# AD_3_V1_01.net
KiCad netlist of a schematic drawn in Altium Designer
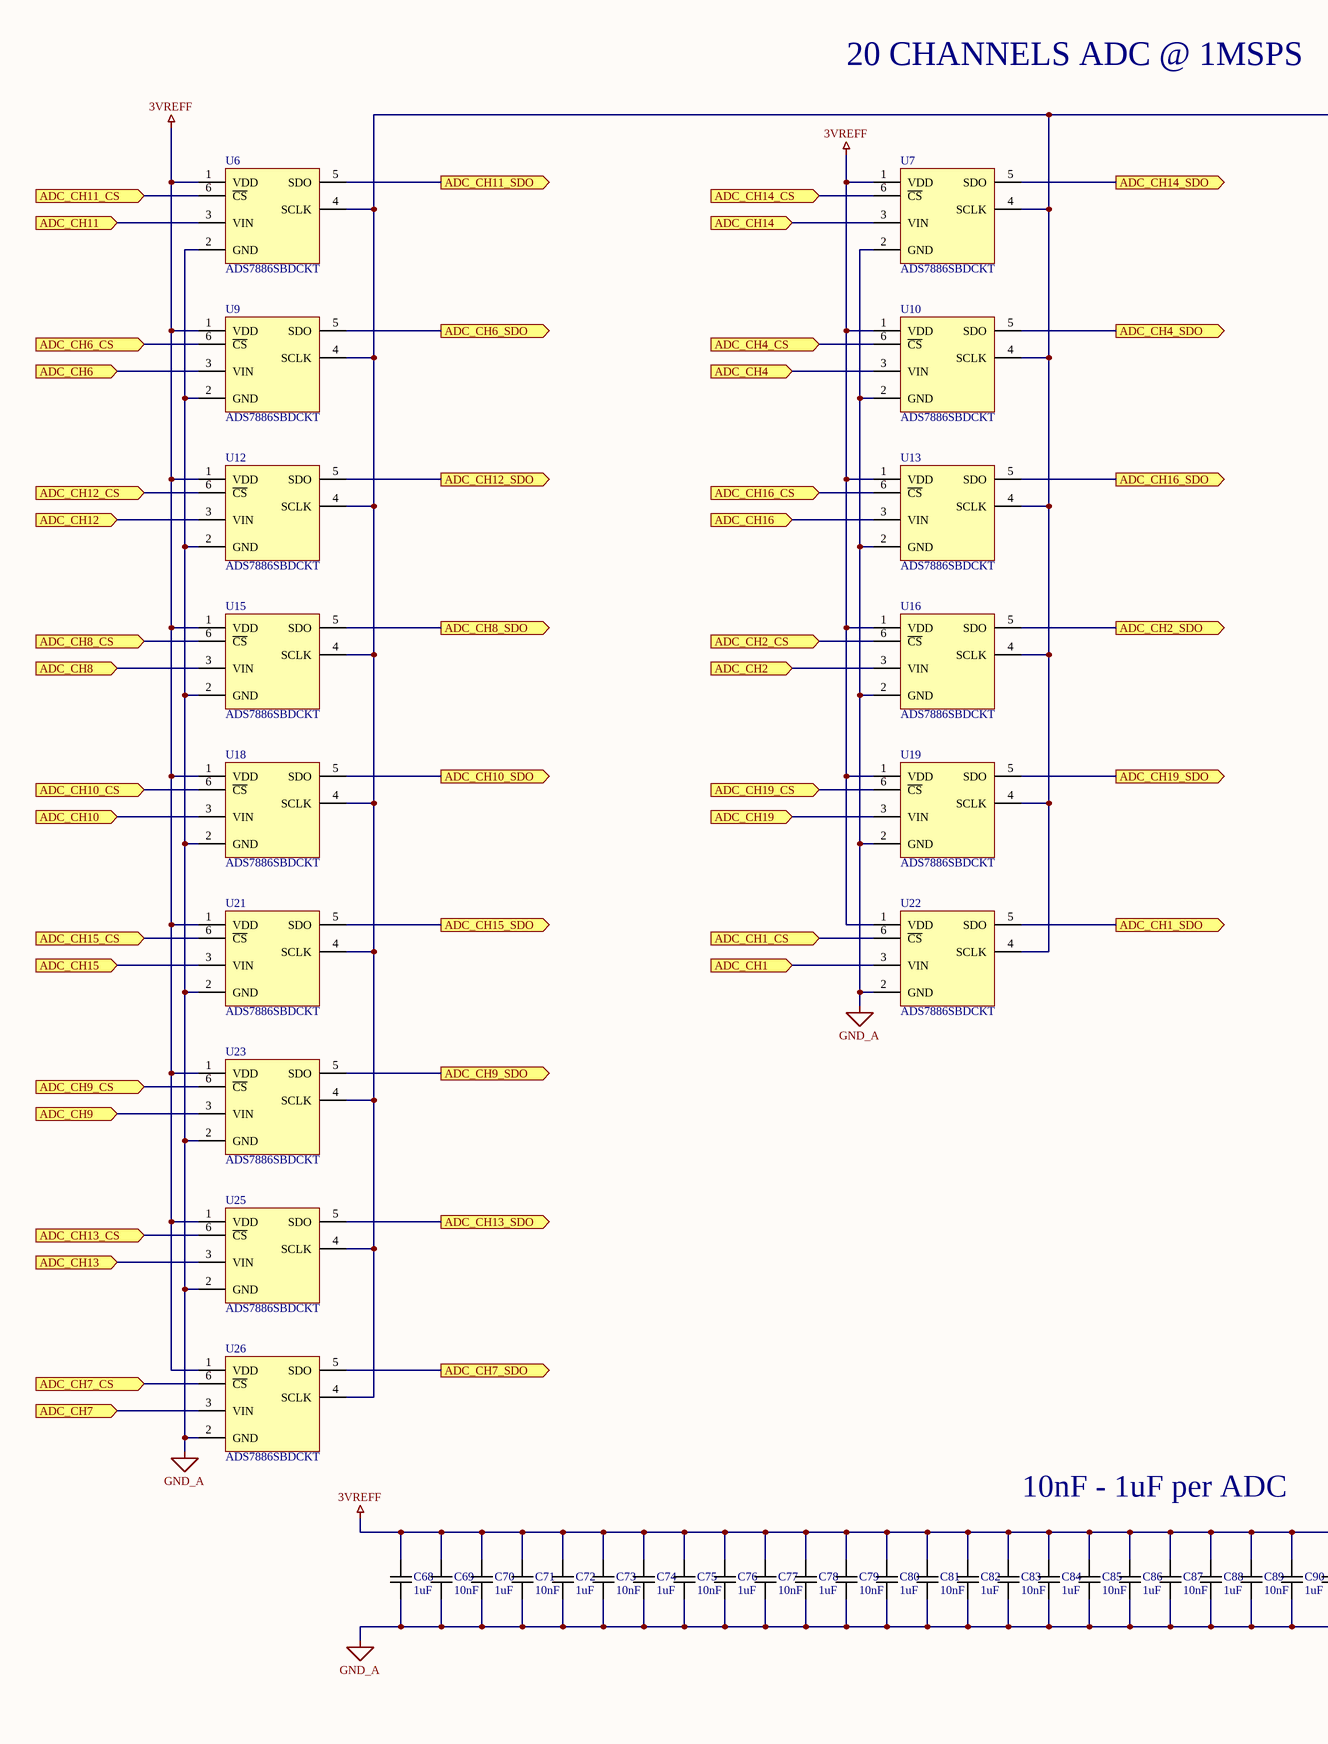
[diagram p0: AD_3_V1_01.SchDoc, left]
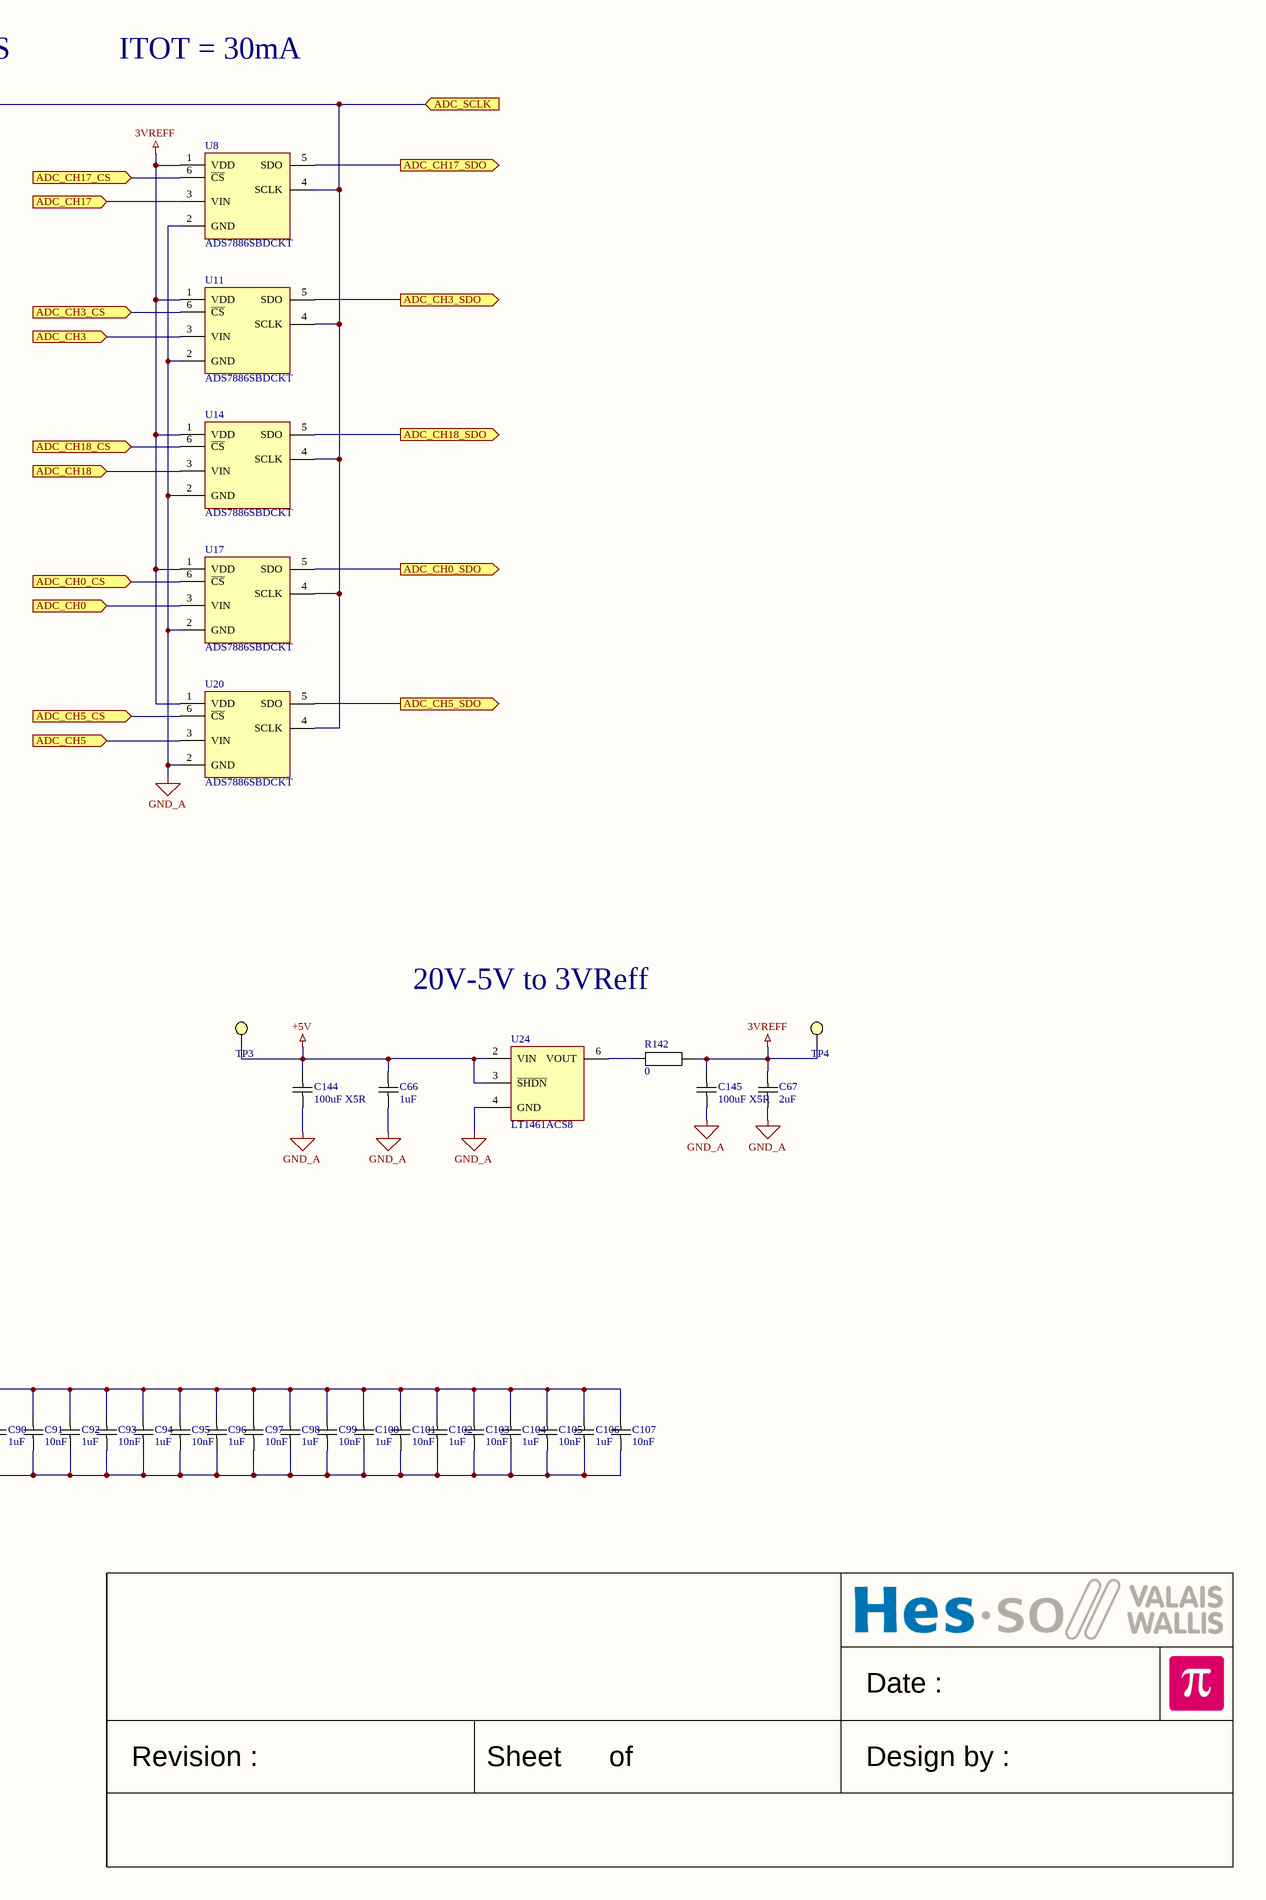
[diagram p1: AD_3_V1_01.SchDoc, right]

(export (version "E")
  (design (tool "Eeschema 10.0.6"))
  (components
    (comp (ref "C66")
      (value "1uF")
      (footprint "CAPACITOR 1608 REFLOW")
      (description "Capacitor")
      (libsource (lib "Capacitor") (part "Capacitor"))
    )
    (comp (ref "C67")
      (value "2uF")
      (footprint "CAPACITOR 1608 REFLOW")
      (description "Capacitor")
      (libsource (lib "Capacitor") (part "Capacitor"))
    )
    (comp (ref "C68")
      (value "1uF")
      (footprint "CAPACITOR 1608 REFLOW")
      (description "Capacitor")
      (libsource (lib "Capacitor") (part "Capacitor"))
    )
    (comp (ref "C69")
      (value "10nF")
      (footprint "CAPACITOR 1608 REFLOW")
      (description "Capacitor")
      (libsource (lib "Capacitor") (part "Capacitor"))
    )
    (comp (ref "C70")
      (value "1uF")
      (footprint "CAPACITOR 1608 REFLOW")
      (description "Capacitor")
      (libsource (lib "Capacitor") (part "Capacitor"))
    )
    (comp (ref "C71")
      (value "10nF")
      (footprint "CAPACITOR 1608 REFLOW")
      (description "Capacitor")
      (libsource (lib "Capacitor") (part "Capacitor"))
    )
    (comp (ref "C72")
      (value "1uF")
      (footprint "CAPACITOR 1608 REFLOW")
      (description "Capacitor")
      (libsource (lib "Capacitor") (part "Capacitor"))
    )
    (comp (ref "C73")
      (value "10nF")
      (footprint "CAPACITOR 1608 REFLOW")
      (description "Capacitor")
      (libsource (lib "Capacitor") (part "Capacitor"))
    )
    (comp (ref "C74")
      (value "1uF")
      (footprint "CAPACITOR 1608 REFLOW")
      (description "Capacitor")
      (libsource (lib "Capacitor") (part "Capacitor"))
    )
    (comp (ref "C75")
      (value "10nF")
      (footprint "CAPACITOR 1608 REFLOW")
      (description "Capacitor")
      (libsource (lib "Capacitor") (part "Capacitor"))
    )
    (comp (ref "C76")
      (value "1uF")
      (footprint "CAPACITOR 1608 REFLOW")
      (description "Capacitor")
      (libsource (lib "Capacitor") (part "Capacitor"))
    )
    (comp (ref "C77")
      (value "10nF")
      (footprint "CAPACITOR 1608 REFLOW")
      (description "Capacitor")
      (libsource (lib "Capacitor") (part "Capacitor"))
    )
    (comp (ref "C78")
      (value "1uF")
      (footprint "CAPACITOR 1608 REFLOW")
      (description "Capacitor")
      (libsource (lib "Capacitor") (part "Capacitor"))
    )
    (comp (ref "C79")
      (value "10nF")
      (footprint "CAPACITOR 1608 REFLOW")
      (description "Capacitor")
      (libsource (lib "Capacitor") (part "Capacitor"))
    )
    (comp (ref "C80")
      (value "1uF")
      (footprint "CAPACITOR 1608 REFLOW")
      (description "Capacitor")
      (libsource (lib "Capacitor") (part "Capacitor"))
    )
    (comp (ref "C81")
      (value "10nF")
      (footprint "CAPACITOR 1608 REFLOW")
      (description "Capacitor")
      (libsource (lib "Capacitor") (part "Capacitor"))
    )
    (comp (ref "C82")
      (value "1uF")
      (footprint "CAPACITOR 1608 REFLOW")
      (description "Capacitor")
      (libsource (lib "Capacitor") (part "Capacitor"))
    )
    (comp (ref "C83")
      (value "10nF")
      (footprint "CAPACITOR 1608 REFLOW")
      (description "Capacitor")
      (libsource (lib "Capacitor") (part "Capacitor"))
    )
    (comp (ref "C84")
      (value "1uF")
      (footprint "CAPACITOR 1608 REFLOW")
      (description "Capacitor")
      (libsource (lib "Capacitor") (part "Capacitor"))
    )
    (comp (ref "C85")
      (value "10nF")
      (footprint "CAPACITOR 1608 REFLOW")
      (description "Capacitor")
      (libsource (lib "Capacitor") (part "Capacitor"))
    )
    (comp (ref "C86")
      (value "1uF")
      (footprint "CAPACITOR 1608 REFLOW")
      (description "Capacitor")
      (libsource (lib "Capacitor") (part "Capacitor"))
    )
    (comp (ref "C87")
      (value "10nF")
      (footprint "CAPACITOR 1608 REFLOW")
      (description "Capacitor")
      (libsource (lib "Capacitor") (part "Capacitor"))
    )
    (comp (ref "C88")
      (value "1uF")
      (footprint "CAPACITOR 1608 REFLOW")
      (description "Capacitor")
      (libsource (lib "Capacitor") (part "Capacitor"))
    )
    (comp (ref "C89")
      (value "10nF")
      (footprint "CAPACITOR 1608 REFLOW")
      (description "Capacitor")
      (libsource (lib "Capacitor") (part "Capacitor"))
    )
    (comp (ref "C90")
      (value "1uF")
      (footprint "CAPACITOR 1608 REFLOW")
      (description "Capacitor")
      (libsource (lib "Capacitor") (part "Capacitor"))
    )
    (comp (ref "C91")
      (value "10nF")
      (footprint "CAPACITOR 1608 REFLOW")
      (description "Capacitor")
      (libsource (lib "Capacitor") (part "Capacitor"))
    )
    (comp (ref "C92")
      (value "1uF")
      (footprint "CAPACITOR 1608 REFLOW")
      (description "Capacitor")
      (libsource (lib "Capacitor") (part "Capacitor"))
    )
    (comp (ref "C93")
      (value "10nF")
      (footprint "CAPACITOR 1608 REFLOW")
      (description "Capacitor")
      (libsource (lib "Capacitor") (part "Capacitor"))
    )
    (comp (ref "C94")
      (value "1uF")
      (footprint "CAPACITOR 1608 REFLOW")
      (description "Capacitor")
      (libsource (lib "Capacitor") (part "Capacitor"))
    )
    (comp (ref "C95")
      (value "10nF")
      (footprint "CAPACITOR 1608 REFLOW")
      (description "Capacitor")
      (libsource (lib "Capacitor") (part "Capacitor"))
    )
    (comp (ref "C96")
      (value "1uF")
      (footprint "CAPACITOR 1608 REFLOW")
      (description "Capacitor")
      (libsource (lib "Capacitor") (part "Capacitor"))
    )
    (comp (ref "C97")
      (value "10nF")
      (footprint "CAPACITOR 1608 REFLOW")
      (description "Capacitor")
      (libsource (lib "Capacitor") (part "Capacitor"))
    )
    (comp (ref "C98")
      (value "1uF")
      (footprint "CAPACITOR 1608 REFLOW")
      (description "Capacitor")
      (libsource (lib "Capacitor") (part "Capacitor"))
    )
    (comp (ref "C99")
      (value "10nF")
      (footprint "CAPACITOR 1608 REFLOW")
      (description "Capacitor")
      (libsource (lib "Capacitor") (part "Capacitor"))
    )
    (comp (ref "C100")
      (value "1uF")
      (footprint "CAPACITOR 1608 REFLOW")
      (description "Capacitor")
      (libsource (lib "Capacitor") (part "Capacitor"))
    )
    (comp (ref "C101")
      (value "10nF")
      (footprint "CAPACITOR 1608 REFLOW")
      (description "Capacitor")
      (libsource (lib "Capacitor") (part "Capacitor"))
    )
    (comp (ref "C102")
      (value "1uF")
      (footprint "CAPACITOR 1608 REFLOW")
      (description "Capacitor")
      (libsource (lib "Capacitor") (part "Capacitor"))
    )
    (comp (ref "C103")
      (value "10nF")
      (footprint "CAPACITOR 1608 REFLOW")
      (description "Capacitor")
      (libsource (lib "Capacitor") (part "Capacitor"))
    )
    (comp (ref "C104")
      (value "1uF")
      (footprint "CAPACITOR 1608 REFLOW")
      (description "Capacitor")
      (libsource (lib "Capacitor") (part "Capacitor"))
    )
    (comp (ref "C105")
      (value "10nF")
      (footprint "CAPACITOR 1608 REFLOW")
      (description "Capacitor")
      (libsource (lib "Capacitor") (part "Capacitor"))
    )
    (comp (ref "C106")
      (value "1uF")
      (footprint "CAPACITOR 1608 REFLOW")
      (description "Capacitor")
      (libsource (lib "Capacitor") (part "Capacitor"))
    )
    (comp (ref "C107")
      (value "10nF")
      (footprint "CAPACITOR 1608 REFLOW")
      (description "Capacitor")
      (libsource (lib "Capacitor") (part "Capacitor"))
    )
    (comp (ref "C144")
      (value "100uF X5R")
      (footprint "CAPACITOR 3216 REFLOW")
      (description "Capacitor")
      (libsource (lib "Capacitor") (part "Capacitor"))
    )
    (comp (ref "C145")
      (value "100uF X5R")
      (footprint "CAPACITOR 3216 REFLOW")
      (description "Capacitor")
      (libsource (lib "Capacitor") (part "Capacitor"))
    )
    (comp (ref "R142")
      (value "0")
      (footprint "RESISTOR 1608 REFLOW")
      (description "Resistor 1% 50V 100mW 1608(0603)")
      (libsource (lib "Resistor") (part "Resistor"))
    )
    (comp (ref "TP3")
      (value "*")
      (footprint "Test Point Keystone Miniature RED")
      (description "Test Point")
      (libsource (lib "Testpoint") (part "Test Point"))
    )
    (comp (ref "TP4")
      (value "*")
      (footprint "Test Point Keystone Miniature RED")
      (description "Test Point")
      (libsource (lib "Testpoint") (part "Test Point"))
    )
    (comp (ref "U6")
      (value "ADS7886SBDCKT")
      (footprint "SOT23-6 P0.95 C1.5x3.0 H1.3")
      (description "12-Bit, 1-MSPS, Micro-Power, Miniature SAR Analog-to-Digital Converters")
      (libsource (lib "Converter") (part "ADS7886SBDCKT"))
    )
    (comp (ref "U7")
      (value "ADS7886SBDCKT")
      (footprint "SOT23-6 P0.95 C1.5x3.0 H1.3")
      (description "12-Bit, 1-MSPS, Micro-Power, Miniature SAR Analog-to-Digital Converters")
      (libsource (lib "Converter") (part "ADS7886SBDCKT"))
    )
    (comp (ref "U8")
      (value "ADS7886SBDCKT")
      (footprint "SOT23-6 P0.95 C1.5x3.0 H1.3")
      (description "12-Bit, 1-MSPS, Micro-Power, Miniature SAR Analog-to-Digital Converters")
      (libsource (lib "Converter") (part "ADS7886SBDCKT"))
    )
    (comp (ref "U9")
      (value "ADS7886SBDCKT")
      (footprint "SOT23-6 P0.95 C1.5x3.0 H1.3")
      (description "12-Bit, 1-MSPS, Micro-Power, Miniature SAR Analog-to-Digital Converters")
      (libsource (lib "Converter") (part "ADS7886SBDCKT"))
    )
    (comp (ref "U10")
      (value "ADS7886SBDCKT")
      (footprint "SOT23-6 P0.95 C1.5x3.0 H1.3")
      (description "12-Bit, 1-MSPS, Micro-Power, Miniature SAR Analog-to-Digital Converters")
      (libsource (lib "Converter") (part "ADS7886SBDCKT"))
    )
    (comp (ref "U11")
      (value "ADS7886SBDCKT")
      (footprint "SOT23-6 P0.95 C1.5x3.0 H1.3")
      (description "12-Bit, 1-MSPS, Micro-Power, Miniature SAR Analog-to-Digital Converters")
      (libsource (lib "Converter") (part "ADS7886SBDCKT"))
    )
    (comp (ref "U12")
      (value "ADS7886SBDCKT")
      (footprint "SOT23-6 P0.95 C1.5x3.0 H1.3")
      (description "12-Bit, 1-MSPS, Micro-Power, Miniature SAR Analog-to-Digital Converters")
      (libsource (lib "Converter") (part "ADS7886SBDCKT"))
    )
    (comp (ref "U13")
      (value "ADS7886SBDCKT")
      (footprint "SOT23-6 P0.95 C1.5x3.0 H1.3")
      (description "12-Bit, 1-MSPS, Micro-Power, Miniature SAR Analog-to-Digital Converters")
      (libsource (lib "Converter") (part "ADS7886SBDCKT"))
    )
    (comp (ref "U14")
      (value "ADS7886SBDCKT")
      (footprint "SOT23-6 P0.95 C1.5x3.0 H1.3")
      (description "12-Bit, 1-MSPS, Micro-Power, Miniature SAR Analog-to-Digital Converters")
      (libsource (lib "Converter") (part "ADS7886SBDCKT"))
    )
    (comp (ref "U15")
      (value "ADS7886SBDCKT")
      (footprint "SOT23-6 P0.95 C1.5x3.0 H1.3")
      (description "12-Bit, 1-MSPS, Micro-Power, Miniature SAR Analog-to-Digital Converters")
      (libsource (lib "Converter") (part "ADS7886SBDCKT"))
    )
    (comp (ref "U16")
      (value "ADS7886SBDCKT")
      (footprint "SOT23-6 P0.95 C1.5x3.0 H1.3")
      (description "12-Bit, 1-MSPS, Micro-Power, Miniature SAR Analog-to-Digital Converters")
      (libsource (lib "Converter") (part "ADS7886SBDCKT"))
    )
    (comp (ref "U17")
      (value "ADS7886SBDCKT")
      (footprint "SOT23-6 P0.95 C1.5x3.0 H1.3")
      (description "12-Bit, 1-MSPS, Micro-Power, Miniature SAR Analog-to-Digital Converters")
      (libsource (lib "Converter") (part "ADS7886SBDCKT"))
    )
    (comp (ref "U18")
      (value "ADS7886SBDCKT")
      (footprint "SOT23-6 P0.95 C1.5x3.0 H1.3")
      (description "12-Bit, 1-MSPS, Micro-Power, Miniature SAR Analog-to-Digital Converters")
      (libsource (lib "Converter") (part "ADS7886SBDCKT"))
    )
    (comp (ref "U19")
      (value "ADS7886SBDCKT")
      (footprint "SOT23-6 P0.95 C1.5x3.0 H1.3")
      (description "12-Bit, 1-MSPS, Micro-Power, Miniature SAR Analog-to-Digital Converters")
      (libsource (lib "Converter") (part "ADS7886SBDCKT"))
    )
    (comp (ref "U20")
      (value "ADS7886SBDCKT")
      (footprint "SOT23-6 P0.95 C1.5x3.0 H1.3")
      (description "12-Bit, 1-MSPS, Micro-Power, Miniature SAR Analog-to-Digital Converters")
      (libsource (lib "Converter") (part "ADS7886SBDCKT"))
    )
    (comp (ref "U21")
      (value "ADS7886SBDCKT")
      (footprint "SOT23-6 P0.95 C1.5x3.0 H1.3")
      (description "12-Bit, 1-MSPS, Micro-Power, Miniature SAR Analog-to-Digital Converters")
      (libsource (lib "Converter") (part "ADS7886SBDCKT"))
    )
    (comp (ref "U22")
      (value "ADS7886SBDCKT")
      (footprint "SOT23-6 P0.95 C1.5x3.0 H1.3")
      (description "12-Bit, 1-MSPS, Micro-Power, Miniature SAR Analog-to-Digital Converters")
      (libsource (lib "Converter") (part "ADS7886SBDCKT"))
    )
    (comp (ref "U23")
      (value "ADS7886SBDCKT")
      (footprint "SOT23-6 P0.95 C1.5x3.0 H1.3")
      (description "12-Bit, 1-MSPS, Micro-Power, Miniature SAR Analog-to-Digital Converters")
      (libsource (lib "Converter") (part "ADS7886SBDCKT"))
    )
    (comp (ref "U24")
      (value "LT1461ACS8")
      (footprint "SO8 P1.27 C4.0X5.0 H1.75")
      (description "Micropower Precision Low Dropout Series Voltage Reference Family")
      (libsource (lib "Regulator") (part "LT1461ACS8"))
    )
    (comp (ref "U25")
      (value "ADS7886SBDCKT")
      (footprint "SOT23-6 P0.95 C1.5x3.0 H1.3")
      (description "12-Bit, 1-MSPS, Micro-Power, Miniature SAR Analog-to-Digital Converters")
      (libsource (lib "Converter") (part "ADS7886SBDCKT"))
    )
    (comp (ref "U26")
      (value "ADS7886SBDCKT")
      (footprint "SOT23-6 P0.95 C1.5x3.0 H1.3")
      (description "12-Bit, 1-MSPS, Micro-Power, Miniature SAR Analog-to-Digital Converters")
      (libsource (lib "Converter") (part "ADS7886SBDCKT"))
    )
  )
  (nets
    (net (code "1") (name "+5V") (class "Default")
      (node (ref "C144") (pin "2") (pinfunction "2_2") (pintype "passive"))
      (node (ref "C66") (pin "2") (pinfunction "2_2") (pintype "passive"))
      (node (ref "TP3") (pin "1") (pinfunction "1_1") (pintype "passive"))
      (node (ref "U24") (pin "2") (pinfunction "VIN_2") (pintype "passive"))
      (node (ref "U24") (pin "3") (pinfunction "~{SHDN}_3") (pintype "passive"))
    )
    (net (code "2") (name "/ADC_CH0") (class "Default")
      (node (ref "U17") (pin "3") (pinfunction "VIN_3") (pintype "passive"))
    )
    (net (code "3") (name "/ADC_CH0_CS") (class "Default")
      (node (ref "U17") (pin "6") (pinfunction "~{CS}_6") (pintype "passive"))
    )
    (net (code "4") (name "/ADC_CH0_SDO") (class "Default")
      (node (ref "U17") (pin "5") (pinfunction "SDO_5") (pintype "passive"))
    )
    (net (code "5") (name "/ADC_CH1") (class "Default")
      (node (ref "U22") (pin "3") (pinfunction "VIN_3") (pintype "passive"))
    )
    (net (code "6") (name "/ADC_CH1_CS") (class "Default")
      (node (ref "U22") (pin "6") (pinfunction "~{CS}_6") (pintype "passive"))
    )
    (net (code "7") (name "/ADC_CH1_SDO") (class "Default")
      (node (ref "U22") (pin "5") (pinfunction "SDO_5") (pintype "passive"))
    )
    (net (code "8") (name "/ADC_CH2") (class "Default")
      (node (ref "U16") (pin "3") (pinfunction "VIN_3") (pintype "passive"))
    )
    (net (code "9") (name "/ADC_CH2_CS") (class "Default")
      (node (ref "U16") (pin "6") (pinfunction "~{CS}_6") (pintype "passive"))
    )
    (net (code "10") (name "/ADC_CH2_SDO") (class "Default")
      (node (ref "U16") (pin "5") (pinfunction "SDO_5") (pintype "passive"))
    )
    (net (code "11") (name "/ADC_CH3") (class "Default")
      (node (ref "U11") (pin "3") (pinfunction "VIN_3") (pintype "passive"))
    )
    (net (code "12") (name "/ADC_CH3_CS") (class "Default")
      (node (ref "U11") (pin "6") (pinfunction "~{CS}_6") (pintype "passive"))
    )
    (net (code "13") (name "/ADC_CH3_SDO") (class "Default")
      (node (ref "U11") (pin "5") (pinfunction "SDO_5") (pintype "passive"))
    )
    (net (code "14") (name "/ADC_CH4") (class "Default")
      (node (ref "U10") (pin "3") (pinfunction "VIN_3") (pintype "passive"))
    )
    (net (code "15") (name "/ADC_CH4_CS") (class "Default")
      (node (ref "U10") (pin "6") (pinfunction "~{CS}_6") (pintype "passive"))
    )
    (net (code "16") (name "/ADC_CH4_SDO") (class "Default")
      (node (ref "U10") (pin "5") (pinfunction "SDO_5") (pintype "passive"))
    )
    (net (code "17") (name "/ADC_CH5") (class "Default")
      (node (ref "U20") (pin "3") (pinfunction "VIN_3") (pintype "passive"))
    )
    (net (code "18") (name "/ADC_CH5_CS") (class "Default")
      (node (ref "U20") (pin "6") (pinfunction "~{CS}_6") (pintype "passive"))
    )
    (net (code "19") (name "/ADC_CH5_SDO") (class "Default")
      (node (ref "U20") (pin "5") (pinfunction "SDO_5") (pintype "passive"))
    )
    (net (code "20") (name "/ADC_CH6") (class "Default")
      (node (ref "U9") (pin "3") (pinfunction "VIN_3") (pintype "passive"))
    )
    (net (code "21") (name "/ADC_CH6_CS") (class "Default")
      (node (ref "U9") (pin "6") (pinfunction "~{CS}_6") (pintype "passive"))
    )
    (net (code "22") (name "/ADC_CH6_SDO") (class "Default")
      (node (ref "U9") (pin "5") (pinfunction "SDO_5") (pintype "passive"))
    )
    (net (code "23") (name "/ADC_CH7") (class "Default")
      (node (ref "U26") (pin "3") (pinfunction "VIN_3") (pintype "passive"))
    )
    (net (code "24") (name "/ADC_CH7_CS") (class "Default")
      (node (ref "U26") (pin "6") (pinfunction "~{CS}_6") (pintype "passive"))
    )
    (net (code "25") (name "/ADC_CH7_SDO") (class "Default")
      (node (ref "U26") (pin "5") (pinfunction "SDO_5") (pintype "passive"))
    )
    (net (code "26") (name "/ADC_CH8") (class "Default")
      (node (ref "U15") (pin "3") (pinfunction "VIN_3") (pintype "passive"))
    )
    (net (code "27") (name "/ADC_CH8_CS") (class "Default")
      (node (ref "U15") (pin "6") (pinfunction "~{CS}_6") (pintype "passive"))
    )
    (net (code "28") (name "/ADC_CH8_SDO") (class "Default")
      (node (ref "U15") (pin "5") (pinfunction "SDO_5") (pintype "passive"))
    )
    (net (code "29") (name "/ADC_CH9") (class "Default")
      (node (ref "U23") (pin "3") (pinfunction "VIN_3") (pintype "passive"))
    )
    (net (code "30") (name "/ADC_CH9_CS") (class "Default")
      (node (ref "U23") (pin "6") (pinfunction "~{CS}_6") (pintype "passive"))
    )
    (net (code "31") (name "/ADC_CH9_SDO") (class "Default")
      (node (ref "U23") (pin "5") (pinfunction "SDO_5") (pintype "passive"))
    )
    (net (code "32") (name "/ADC_CH10") (class "Default")
      (node (ref "U18") (pin "3") (pinfunction "VIN_3") (pintype "passive"))
    )
    (net (code "33") (name "/ADC_CH10_CS") (class "Default")
      (node (ref "U18") (pin "6") (pinfunction "~{CS}_6") (pintype "passive"))
    )
    (net (code "34") (name "/ADC_CH10_SDO") (class "Default")
      (node (ref "U18") (pin "5") (pinfunction "SDO_5") (pintype "passive"))
    )
    (net (code "35") (name "/ADC_CH11") (class "Default")
      (node (ref "U6") (pin "3") (pinfunction "VIN_3") (pintype "passive"))
    )
    (net (code "36") (name "/ADC_CH11_CS") (class "Default")
      (node (ref "U6") (pin "6") (pinfunction "~{CS}_6") (pintype "passive"))
    )
    (net (code "37") (name "/ADC_CH11_SDO") (class "Default")
      (node (ref "U6") (pin "5") (pinfunction "SDO_5") (pintype "passive"))
    )
    (net (code "38") (name "/ADC_CH12") (class "Default")
      (node (ref "U12") (pin "3") (pinfunction "VIN_3") (pintype "passive"))
    )
    (net (code "39") (name "/ADC_CH12_CS") (class "Default")
      (node (ref "U12") (pin "6") (pinfunction "~{CS}_6") (pintype "passive"))
    )
    (net (code "40") (name "/ADC_CH12_SDO") (class "Default")
      (node (ref "U12") (pin "5") (pinfunction "SDO_5") (pintype "passive"))
    )
    (net (code "41") (name "/ADC_CH13") (class "Default")
      (node (ref "U25") (pin "3") (pinfunction "VIN_3") (pintype "passive"))
    )
    (net (code "42") (name "/ADC_CH13_CS") (class "Default")
      (node (ref "U25") (pin "6") (pinfunction "~{CS}_6") (pintype "passive"))
    )
    (net (code "43") (name "/ADC_CH13_SDO") (class "Default")
      (node (ref "U25") (pin "5") (pinfunction "SDO_5") (pintype "passive"))
    )
    (net (code "44") (name "/ADC_CH14") (class "Default")
      (node (ref "U7") (pin "3") (pinfunction "VIN_3") (pintype "passive"))
    )
    (net (code "45") (name "/ADC_CH14_CS") (class "Default")
      (node (ref "U7") (pin "6") (pinfunction "~{CS}_6") (pintype "passive"))
    )
    (net (code "46") (name "/ADC_CH14_SDO") (class "Default")
      (node (ref "U7") (pin "5") (pinfunction "SDO_5") (pintype "passive"))
    )
    (net (code "47") (name "/ADC_CH15") (class "Default")
      (node (ref "U21") (pin "3") (pinfunction "VIN_3") (pintype "passive"))
    )
    (net (code "48") (name "/ADC_CH15_CS") (class "Default")
      (node (ref "U21") (pin "6") (pinfunction "~{CS}_6") (pintype "passive"))
    )
    (net (code "49") (name "/ADC_CH15_SDO") (class "Default")
      (node (ref "U21") (pin "5") (pinfunction "SDO_5") (pintype "passive"))
    )
    (net (code "50") (name "/ADC_CH16") (class "Default")
      (node (ref "U13") (pin "3") (pinfunction "VIN_3") (pintype "passive"))
    )
    (net (code "51") (name "/ADC_CH16_CS") (class "Default")
      (node (ref "U13") (pin "6") (pinfunction "~{CS}_6") (pintype "passive"))
    )
    (net (code "52") (name "/ADC_CH16_SDO") (class "Default")
      (node (ref "U13") (pin "5") (pinfunction "SDO_5") (pintype "passive"))
    )
    (net (code "53") (name "/ADC_CH17") (class "Default")
      (node (ref "U8") (pin "3") (pinfunction "VIN_3") (pintype "passive"))
    )
    (net (code "54") (name "/ADC_CH17_CS") (class "Default")
      (node (ref "U8") (pin "6") (pinfunction "~{CS}_6") (pintype "passive"))
    )
    (net (code "55") (name "/ADC_CH17_SDO") (class "Default")
      (node (ref "U8") (pin "5") (pinfunction "SDO_5") (pintype "passive"))
    )
    (net (code "56") (name "/ADC_CH18") (class "Default")
      (node (ref "U14") (pin "3") (pinfunction "VIN_3") (pintype "passive"))
    )
    (net (code "57") (name "/ADC_CH18_CS") (class "Default")
      (node (ref "U14") (pin "6") (pinfunction "~{CS}_6") (pintype "passive"))
    )
    (net (code "58") (name "/ADC_CH18_SDO") (class "Default")
      (node (ref "U14") (pin "5") (pinfunction "SDO_5") (pintype "passive"))
    )
    (net (code "59") (name "/ADC_CH19") (class "Default")
      (node (ref "U19") (pin "3") (pinfunction "VIN_3") (pintype "passive"))
    )
    (net (code "60") (name "/ADC_CH19_CS") (class "Default")
      (node (ref "U19") (pin "6") (pinfunction "~{CS}_6") (pintype "passive"))
    )
    (net (code "61") (name "/ADC_CH19_SDO") (class "Default")
      (node (ref "U19") (pin "5") (pinfunction "SDO_5") (pintype "passive"))
    )
    (net (code "62") (name "/ADC_SCLK") (class "Default")
      (node (ref "U10") (pin "4") (pinfunction "SCLK_4") (pintype "passive"))
      (node (ref "U11") (pin "4") (pinfunction "SCLK_4") (pintype "passive"))
      (node (ref "U12") (pin "4") (pinfunction "SCLK_4") (pintype "passive"))
      (node (ref "U13") (pin "4") (pinfunction "SCLK_4") (pintype "passive"))
      (node (ref "U14") (pin "4") (pinfunction "SCLK_4") (pintype "passive"))
      (node (ref "U15") (pin "4") (pinfunction "SCLK_4") (pintype "passive"))
      (node (ref "U16") (pin "4") (pinfunction "SCLK_4") (pintype "passive"))
      (node (ref "U17") (pin "4") (pinfunction "SCLK_4") (pintype "passive"))
      (node (ref "U18") (pin "4") (pinfunction "SCLK_4") (pintype "passive"))
      (node (ref "U19") (pin "4") (pinfunction "SCLK_4") (pintype "passive"))
      (node (ref "U20") (pin "4") (pinfunction "SCLK_4") (pintype "passive"))
      (node (ref "U21") (pin "4") (pinfunction "SCLK_4") (pintype "passive"))
      (node (ref "U22") (pin "4") (pinfunction "SCLK_4") (pintype "passive"))
      (node (ref "U23") (pin "4") (pinfunction "SCLK_4") (pintype "passive"))
      (node (ref "U25") (pin "4") (pinfunction "SCLK_4") (pintype "passive"))
      (node (ref "U26") (pin "4") (pinfunction "SCLK_4") (pintype "passive"))
      (node (ref "U6") (pin "4") (pinfunction "SCLK_4") (pintype "passive"))
      (node (ref "U7") (pin "4") (pinfunction "SCLK_4") (pintype "passive"))
      (node (ref "U8") (pin "4") (pinfunction "SCLK_4") (pintype "passive"))
      (node (ref "U9") (pin "4") (pinfunction "SCLK_4") (pintype "passive"))
    )
    (net (code "63") (name "3VREFF") (class "Default")
      (node (ref "C100") (pin "2") (pinfunction "2_2") (pintype "passive"))
      (node (ref "C101") (pin "2") (pinfunction "2_2") (pintype "passive"))
      (node (ref "C102") (pin "2") (pinfunction "2_2") (pintype "passive"))
      (node (ref "C103") (pin "2") (pinfunction "2_2") (pintype "passive"))
      (node (ref "C104") (pin "2") (pinfunction "2_2") (pintype "passive"))
      (node (ref "C105") (pin "2") (pinfunction "2_2") (pintype "passive"))
      (node (ref "C106") (pin "2") (pinfunction "2_2") (pintype "passive"))
      (node (ref "C107") (pin "2") (pinfunction "2_2") (pintype "passive"))
      (node (ref "C145") (pin "2") (pinfunction "2_2") (pintype "passive"))
      (node (ref "C67") (pin "2") (pinfunction "2_2") (pintype "passive"))
      (node (ref "C68") (pin "2") (pinfunction "2_2") (pintype "passive"))
      (node (ref "C69") (pin "2") (pinfunction "2_2") (pintype "passive"))
      (node (ref "C70") (pin "2") (pinfunction "2_2") (pintype "passive"))
      (node (ref "C71") (pin "2") (pinfunction "2_2") (pintype "passive"))
      (node (ref "C72") (pin "2") (pinfunction "2_2") (pintype "passive"))
      (node (ref "C73") (pin "2") (pinfunction "2_2") (pintype "passive"))
      (node (ref "C74") (pin "2") (pinfunction "2_2") (pintype "passive"))
      (node (ref "C75") (pin "2") (pinfunction "2_2") (pintype "passive"))
      (node (ref "C76") (pin "2") (pinfunction "2_2") (pintype "passive"))
      (node (ref "C77") (pin "2") (pinfunction "2_2") (pintype "passive"))
      (node (ref "C78") (pin "2") (pinfunction "2_2") (pintype "passive"))
      (node (ref "C79") (pin "2") (pinfunction "2_2") (pintype "passive"))
      (node (ref "C80") (pin "2") (pinfunction "2_2") (pintype "passive"))
      (node (ref "C81") (pin "2") (pinfunction "2_2") (pintype "passive"))
      (node (ref "C82") (pin "2") (pinfunction "2_2") (pintype "passive"))
      (node (ref "C83") (pin "2") (pinfunction "2_2") (pintype "passive"))
      (node (ref "C84") (pin "2") (pinfunction "2_2") (pintype "passive"))
      (node (ref "C85") (pin "2") (pinfunction "2_2") (pintype "passive"))
      (node (ref "C86") (pin "2") (pinfunction "2_2") (pintype "passive"))
      (node (ref "C87") (pin "2") (pinfunction "2_2") (pintype "passive"))
      (node (ref "C88") (pin "2") (pinfunction "2_2") (pintype "passive"))
      (node (ref "C89") (pin "2") (pinfunction "2_2") (pintype "passive"))
      (node (ref "C90") (pin "2") (pinfunction "2_2") (pintype "passive"))
      (node (ref "C91") (pin "2") (pinfunction "2_2") (pintype "passive"))
      (node (ref "C92") (pin "2") (pinfunction "2_2") (pintype "passive"))
      (node (ref "C93") (pin "2") (pinfunction "2_2") (pintype "passive"))
      (node (ref "C94") (pin "2") (pinfunction "2_2") (pintype "passive"))
      (node (ref "C95") (pin "2") (pinfunction "2_2") (pintype "passive"))
      (node (ref "C96") (pin "2") (pinfunction "2_2") (pintype "passive"))
      (node (ref "C97") (pin "2") (pinfunction "2_2") (pintype "passive"))
      (node (ref "C98") (pin "2") (pinfunction "2_2") (pintype "passive"))
      (node (ref "C99") (pin "2") (pinfunction "2_2") (pintype "passive"))
      (node (ref "R142") (pin "2") (pinfunction "2_2") (pintype "passive"))
      (node (ref "TP4") (pin "1") (pinfunction "1_1") (pintype "passive"))
      (node (ref "U10") (pin "1") (pinfunction "VDD_1") (pintype "passive"))
      (node (ref "U11") (pin "1") (pinfunction "VDD_1") (pintype "passive"))
      (node (ref "U12") (pin "1") (pinfunction "VDD_1") (pintype "passive"))
      (node (ref "U13") (pin "1") (pinfunction "VDD_1") (pintype "passive"))
      (node (ref "U14") (pin "1") (pinfunction "VDD_1") (pintype "passive"))
      (node (ref "U15") (pin "1") (pinfunction "VDD_1") (pintype "passive"))
      (node (ref "U16") (pin "1") (pinfunction "VDD_1") (pintype "passive"))
      (node (ref "U17") (pin "1") (pinfunction "VDD_1") (pintype "passive"))
      (node (ref "U18") (pin "1") (pinfunction "VDD_1") (pintype "passive"))
      (node (ref "U19") (pin "1") (pinfunction "VDD_1") (pintype "passive"))
      (node (ref "U20") (pin "1") (pinfunction "VDD_1") (pintype "passive"))
      (node (ref "U21") (pin "1") (pinfunction "VDD_1") (pintype "passive"))
      (node (ref "U22") (pin "1") (pinfunction "VDD_1") (pintype "passive"))
      (node (ref "U23") (pin "1") (pinfunction "VDD_1") (pintype "passive"))
      (node (ref "U25") (pin "1") (pinfunction "VDD_1") (pintype "passive"))
      (node (ref "U26") (pin "1") (pinfunction "VDD_1") (pintype "passive"))
      (node (ref "U6") (pin "1") (pinfunction "VDD_1") (pintype "passive"))
      (node (ref "U7") (pin "1") (pinfunction "VDD_1") (pintype "passive"))
      (node (ref "U8") (pin "1") (pinfunction "VDD_1") (pintype "passive"))
      (node (ref "U9") (pin "1") (pinfunction "VDD_1") (pintype "passive"))
    )
    (net (code "64") (name "GND_A") (class "Default")
      (node (ref "C100") (pin "1") (pinfunction "1_1") (pintype "passive"))
      (node (ref "C101") (pin "1") (pinfunction "1_1") (pintype "passive"))
      (node (ref "C102") (pin "1") (pinfunction "1_1") (pintype "passive"))
      (node (ref "C103") (pin "1") (pinfunction "1_1") (pintype "passive"))
      (node (ref "C104") (pin "1") (pinfunction "1_1") (pintype "passive"))
      (node (ref "C105") (pin "1") (pinfunction "1_1") (pintype "passive"))
      (node (ref "C106") (pin "1") (pinfunction "1_1") (pintype "passive"))
      (node (ref "C107") (pin "1") (pinfunction "1_1") (pintype "passive"))
      (node (ref "C144") (pin "1") (pinfunction "1_1") (pintype "passive"))
      (node (ref "C145") (pin "1") (pinfunction "1_1") (pintype "passive"))
      (node (ref "C66") (pin "1") (pinfunction "1_1") (pintype "passive"))
      (node (ref "C67") (pin "1") (pinfunction "1_1") (pintype "passive"))
      (node (ref "C68") (pin "1") (pinfunction "1_1") (pintype "passive"))
      (node (ref "C69") (pin "1") (pinfunction "1_1") (pintype "passive"))
      (node (ref "C70") (pin "1") (pinfunction "1_1") (pintype "passive"))
      (node (ref "C71") (pin "1") (pinfunction "1_1") (pintype "passive"))
      (node (ref "C72") (pin "1") (pinfunction "1_1") (pintype "passive"))
      (node (ref "C73") (pin "1") (pinfunction "1_1") (pintype "passive"))
      (node (ref "C74") (pin "1") (pinfunction "1_1") (pintype "passive"))
      (node (ref "C75") (pin "1") (pinfunction "1_1") (pintype "passive"))
      (node (ref "C76") (pin "1") (pinfunction "1_1") (pintype "passive"))
      (node (ref "C77") (pin "1") (pinfunction "1_1") (pintype "passive"))
      (node (ref "C78") (pin "1") (pinfunction "1_1") (pintype "passive"))
      (node (ref "C79") (pin "1") (pinfunction "1_1") (pintype "passive"))
      (node (ref "C80") (pin "1") (pinfunction "1_1") (pintype "passive"))
      (node (ref "C81") (pin "1") (pinfunction "1_1") (pintype "passive"))
      (node (ref "C82") (pin "1") (pinfunction "1_1") (pintype "passive"))
      (node (ref "C83") (pin "1") (pinfunction "1_1") (pintype "passive"))
      (node (ref "C84") (pin "1") (pinfunction "1_1") (pintype "passive"))
      (node (ref "C85") (pin "1") (pinfunction "1_1") (pintype "passive"))
      (node (ref "C86") (pin "1") (pinfunction "1_1") (pintype "passive"))
      (node (ref "C87") (pin "1") (pinfunction "1_1") (pintype "passive"))
      (node (ref "C88") (pin "1") (pinfunction "1_1") (pintype "passive"))
      (node (ref "C89") (pin "1") (pinfunction "1_1") (pintype "passive"))
      (node (ref "C90") (pin "1") (pinfunction "1_1") (pintype "passive"))
      (node (ref "C91") (pin "1") (pinfunction "1_1") (pintype "passive"))
      (node (ref "C92") (pin "1") (pinfunction "1_1") (pintype "passive"))
      (node (ref "C93") (pin "1") (pinfunction "1_1") (pintype "passive"))
      (node (ref "C94") (pin "1") (pinfunction "1_1") (pintype "passive"))
      (node (ref "C95") (pin "1") (pinfunction "1_1") (pintype "passive"))
      (node (ref "C96") (pin "1") (pinfunction "1_1") (pintype "passive"))
      (node (ref "C97") (pin "1") (pinfunction "1_1") (pintype "passive"))
      (node (ref "C98") (pin "1") (pinfunction "1_1") (pintype "passive"))
      (node (ref "C99") (pin "1") (pinfunction "1_1") (pintype "passive"))
      (node (ref "U10") (pin "2") (pinfunction "GND_2") (pintype "passive"))
      (node (ref "U11") (pin "2") (pinfunction "GND_2") (pintype "passive"))
      (node (ref "U12") (pin "2") (pinfunction "GND_2") (pintype "passive"))
      (node (ref "U13") (pin "2") (pinfunction "GND_2") (pintype "passive"))
      (node (ref "U14") (pin "2") (pinfunction "GND_2") (pintype "passive"))
      (node (ref "U15") (pin "2") (pinfunction "GND_2") (pintype "passive"))
      (node (ref "U16") (pin "2") (pinfunction "GND_2") (pintype "passive"))
      (node (ref "U17") (pin "2") (pinfunction "GND_2") (pintype "passive"))
      (node (ref "U18") (pin "2") (pinfunction "GND_2") (pintype "passive"))
      (node (ref "U19") (pin "2") (pinfunction "GND_2") (pintype "passive"))
      (node (ref "U20") (pin "2") (pinfunction "GND_2") (pintype "passive"))
      (node (ref "U21") (pin "2") (pinfunction "GND_2") (pintype "passive"))
      (node (ref "U22") (pin "2") (pinfunction "GND_2") (pintype "passive"))
      (node (ref "U23") (pin "2") (pinfunction "GND_2") (pintype "passive"))
      (node (ref "U24") (pin "4") (pinfunction "GND_4") (pintype "passive"))
      (node (ref "U25") (pin "2") (pinfunction "GND_2") (pintype "passive"))
      (node (ref "U26") (pin "2") (pinfunction "GND_2") (pintype "passive"))
      (node (ref "U6") (pin "2") (pinfunction "GND_2") (pintype "passive"))
      (node (ref "U7") (pin "2") (pinfunction "GND_2") (pintype "passive"))
      (node (ref "U8") (pin "2") (pinfunction "GND_2") (pintype "passive"))
      (node (ref "U9") (pin "2") (pinfunction "GND_2") (pintype "passive"))
    )
    (net (code "65") (name "Net-(U24-VOUT)") (class "Default")
      (node (ref "R142") (pin "1") (pinfunction "1_1") (pintype "passive"))
      (node (ref "U24") (pin "6") (pinfunction "VOUT_6") (pintype "passive"))
    )
  )
)
